# TalkingClock.net
KiCad netlist of a schematic drawn in EAGLE
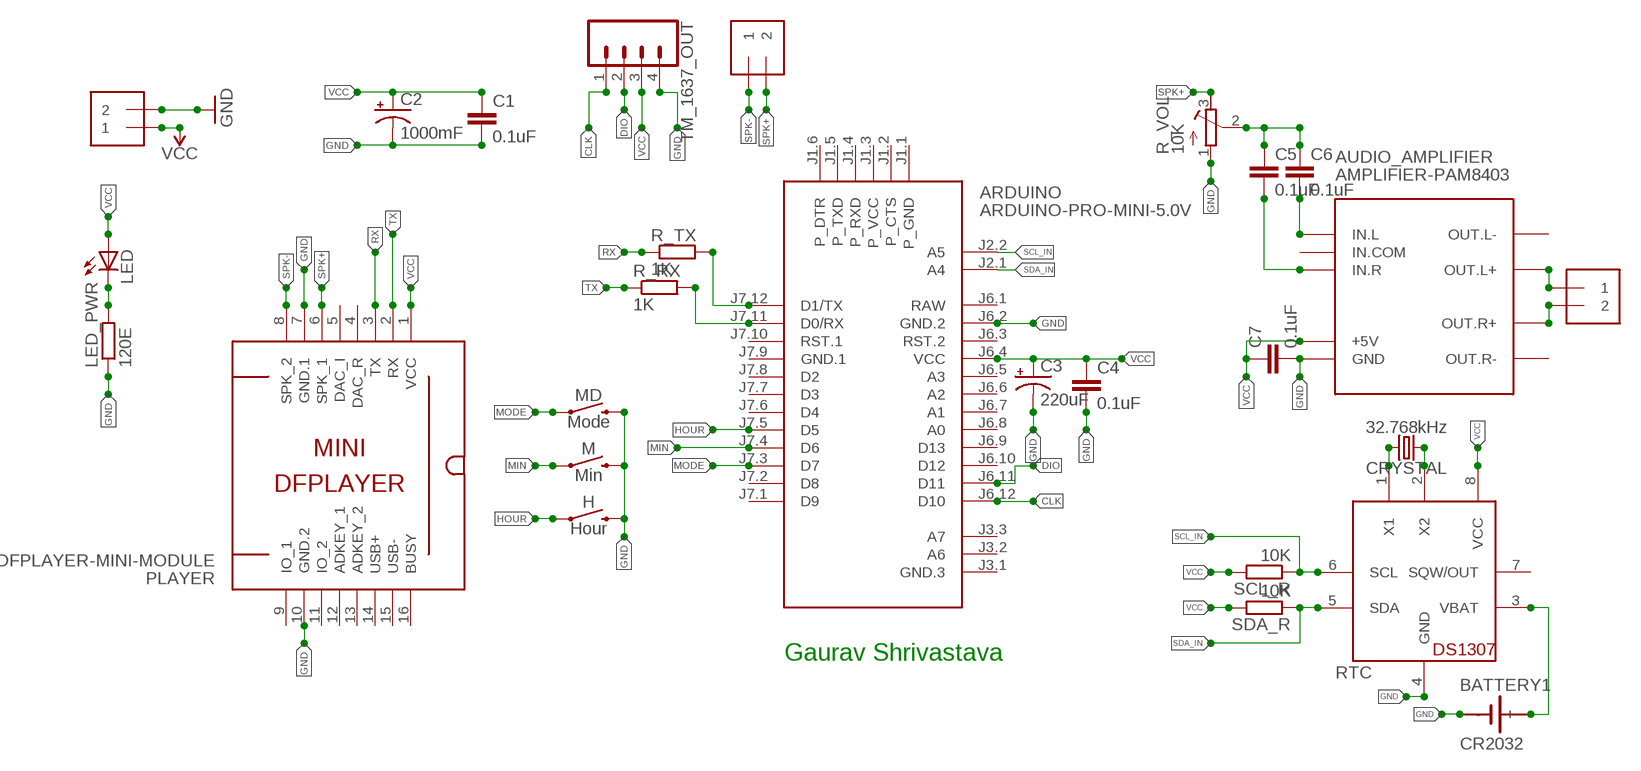
[diagram p0: schematic, sheet 1]

(export (version "E")
  (design (tool "Eeschema 10.0.6"))
  (components
    (comp (ref "ARDUINO")
      (value "ARDUINO-PRO-MINI-5.0V")
      (footprint "eagle-import:ARDUINO-PRO-MINI")
      (libsource (lib "eagle-import") (part "ARDUINO-PRO-MINI-5.0V"))
    )
    (comp (ref "AUDIO_AMPLIFIER")
      (value "AMPLIFIER-PAM8403")
      (footprint "eagle-import:AMPLIFIER-PAM8403")
      (libsource (lib "eagle-import") (part "AMPLIFIER-PAM8403"))
    )
    (comp (ref "BATTERY1")
      (value "CR2032")
      (footprint "eagle-import:SN2032")
      (libsource (lib "eagle-import") (part "SN2032"))
    )
    (comp (ref "C1")
      (value "0.1uF")
      (footprint "eagle-import:CAP-PTH-SMALL-KIT")
      (libsource (lib "eagle-import") (part "0.1UF-KIT-EZ-50V-20%"))
    )
    (comp (ref "C2")
      (value "1000mF")
      (footprint "eagle-import:CPOL-RADIAL-5MM-10MM")
      (libsource (lib "eagle-import") (part "1000UF-RADIAL-5MM-25V-20%"))
    )
    (comp (ref "C3")
      (value "220uF")
      (footprint "eagle-import:CPOL-RADIAL-2.5MM-6.5MM")
      (libsource (lib "eagle-import") (part "100UF-POLAR-RADIAL-2.5MM-25V-20%"))
    )
    (comp (ref "C4")
      (value "0.1uF")
      (footprint "eagle-import:CAP-PTH-SMALL-KIT")
      (libsource (lib "eagle-import") (part "0.1UF-KIT-EZ-50V-20%"))
    )
    (comp (ref "C5")
      (value "0.1uF")
      (footprint "eagle-import:CAP-PTH-SMALL-KIT")
      (libsource (lib "eagle-import") (part "0.1UF-KIT-EZ-50V-20%"))
    )
    (comp (ref "C6")
      (value "0.1uF")
      (footprint "eagle-import:CAP-PTH-SMALL-KIT")
      (libsource (lib "eagle-import") (part "0.1UF-KIT-EZ-50V-20%"))
    )
    (comp (ref "C7")
      (value "0.1uF")
      (footprint "eagle-import:CAP-PTH-SMALL-KIT")
      (libsource (lib "eagle-import") (part "0.1UF-KIT-EZ-50V-20%"))
    )
    (comp (ref "CRYSTAL")
      (value "32.768kHz")
      (footprint "eagle-import:CRYSTAL-PTH-2X6-CYL")
      (libsource (lib "eagle-import") (part "CRYSTAL-32.768KHZPTH-2X6"))
    )
    (comp (ref "H")
      (value "Hour")
      (footprint "eagle-import:TACTILE_SWITCH_PTH_6.0MM")
      (libsource (lib "eagle-import") (part "MOMENTARY-SWITCH-SPST-PTH-6.0MM"))
    )
    (comp (ref "LED")
      (value "LED5MM")
      (footprint "eagle-import:LED5MM")
      (libsource (lib "eagle-import") (part "LED5MM"))
    )
    (comp (ref "LED_PWR")
      (value "120E")
      (footprint "eagle-import:0204_7")
      (libsource (lib "eagle-import") (part "R-EU_0204/7"))
    )
    (comp (ref "M")
      (value "Min")
      (footprint "eagle-import:TACTILE_SWITCH_PTH_6.0MM")
      (libsource (lib "eagle-import") (part "MOMENTARY-SWITCH-SPST-PTH-6.0MM"))
    )
    (comp (ref "MD")
      (value "Mode")
      (footprint "eagle-import:TACTILE_SWITCH_PTH_6.0MM")
      (libsource (lib "eagle-import") (part "MOMENTARY-SWITCH-SPST-PTH-6.0MM"))
    )
    (comp (ref "PLAYER")
      (value "DFPLAYER-MINI-MODULE")
      (footprint "eagle-import:DFPLAYER-MINI-MODULE")
      (libsource (lib "eagle-import") (part "DFPLAYER-MINI-MODULE"))
    )
    (comp (ref "POWER-5-V")
      (value "SPEAKER")
      (footprint "eagle-import:1X2-3.5MM")
      (libsource (lib "eagle-import") (part "1X2-3.5MM"))
    )
    (comp (ref "PRE_SPK_OUT")
      (value "SPEAKER")
      (footprint "eagle-import:1X2-3.5MM")
      (libsource (lib "eagle-import") (part "1X2-3.5MM"))
    )
    (comp (ref "RTC")
      (value "DS1307")
      (footprint "eagle-import:DIL08")
      (libsource (lib "eagle-import") (part "DS1307"))
    )
    (comp (ref "R_RX")
      (value "1K")
      (footprint "eagle-import:0204_7")
      (libsource (lib "eagle-import") (part "R-EU_0204/7"))
    )
    (comp (ref "R_TX")
      (value "1K")
      (footprint "eagle-import:0204_7")
      (libsource (lib "eagle-import") (part "R-EU_0204/7"))
    )
    (comp (ref "R_VOL")
      (value "10K")
      (footprint "eagle-import:RTRIM4G_J")
      (libsource (lib "eagle-import") (part "R-TRIMM4G/J"))
    )
    (comp (ref "SCL_R")
      (value "10K")
      (footprint "eagle-import:0204_7")
      (libsource (lib "eagle-import") (part "R-EU_0204/7"))
    )
    (comp (ref "SDA_R")
      (value "10K")
      (footprint "eagle-import:0204_7")
      (libsource (lib "eagle-import") (part "R-EU_0204/7"))
    )
    (comp (ref "SPEAKER")
      (value "SPEAKER")
      (footprint "eagle-import:1X2-3.5MM")
      (libsource (lib "eagle-import") (part "1X2-3.5MM"))
    )
    (comp (ref "TM_1637_OUT")
      (value "CONN_04")
      (footprint "eagle-import:1X04")
      (libsource (lib "eagle-import") (part "CONN_04"))
    )
  )
  (nets
    (net (code "1") (name "/GND.1") (class "Default")
      (node (ref "ARDUINO") (pin "J7.9") (pinfunction "GND.1_J7.9") (pintype "power_in"))
    )
    (net (code "2") (name "/RAW") (class "Default")
      (node (ref "ARDUINO") (pin "J6.1") (pinfunction "RAW_J6.1") (pintype "power_in"))
    )
    (net (code "3") (name "CLK") (class "Default")
      (node (ref "ARDUINO") (pin "J6.12") (pinfunction "D10_J6.12") (pintype "bidirectional"))
      (node (ref "TM_1637_OUT") (pin "1") (pinfunction "1_1") (pintype "passive"))
    )
    (net (code "4") (name "DIO") (class "Default")
      (node (ref "ARDUINO") (pin "J6.11") (pinfunction "D11_J6.11") (pintype "bidirectional"))
      (node (ref "TM_1637_OUT") (pin "2") (pinfunction "2_2") (pintype "passive"))
    )
    (net (code "5") (name "GND") (class "Default")
      (node (ref "ARDUINO") (pin "J6.2") (pinfunction "GND.2_J6.2") (pintype "power_in"))
      (node (ref "AUDIO_AMPLIFIER") (pin "GND") (pinfunction "GND_GND") (pintype "power_in"))
      (node (ref "BATTERY1") (pin "-") (pinfunction "-_-") (pintype "passive"))
      (node (ref "C1") (pin "2") (pinfunction "2_2") (pintype "passive"))
      (node (ref "C2") (pin "-") (pinfunction "-_-") (pintype "passive"))
      (node (ref "C3") (pin "2") (pinfunction "-_2") (pintype "passive"))
      (node (ref "C4") (pin "2") (pinfunction "2_2") (pintype "passive"))
      (node (ref "C7") (pin "2") (pinfunction "2_2") (pintype "passive"))
      (node (ref "H") (pin "3") (pinfunction "2_3") (pintype "passive"))
      (node (ref "LED_PWR") (pin "1") (pinfunction "1_1") (pintype "passive"))
      (node (ref "M") (pin "3") (pinfunction "2_3") (pintype "passive"))
      (node (ref "MD") (pin "3") (pinfunction "2_3") (pintype "passive"))
      (node (ref "PLAYER") (pin "10") (pinfunction "GND.2_10") (pintype "power_in"))
      (node (ref "PLAYER") (pin "7") (pinfunction "GND.1_7") (pintype "power_in"))
      (node (ref "POWER-5-V") (pin "2") (pinfunction "2_2") (pintype "passive"))
      (node (ref "RTC") (pin "4") (pinfunction "GND_4") (pintype "power_in"))
      (node (ref "R_VOL") (pin "1") (pinfunction "A_1") (pintype "passive"))
      (node (ref "TM_1637_OUT") (pin "4") (pinfunction "4_4") (pintype "passive"))
    )
    (net (code "6") (name "HOUR") (class "Default")
      (node (ref "ARDUINO") (pin "J7.5") (pinfunction "D5_J7.5") (pintype "bidirectional"))
      (node (ref "H") (pin "1") (pinfunction "1_1") (pintype "passive"))
    )
    (net (code "7") (name "MIN") (class "Default")
      (node (ref "ARDUINO") (pin "J7.4") (pinfunction "D6_J7.4") (pintype "bidirectional"))
      (node (ref "M") (pin "1") (pinfunction "1_1") (pintype "passive"))
    )
    (net (code "8") (name "MODE") (class "Default")
      (node (ref "ARDUINO") (pin "J7.3") (pinfunction "D7_J7.3") (pintype "bidirectional"))
      (node (ref "MD") (pin "1") (pinfunction "1_1") (pintype "passive"))
    )
    (net (code "9") (name "Net-(ARDUINO-D0{slash}RX)") (class "Default")
      (node (ref "ARDUINO") (pin "J7.11") (pinfunction "D0/RX_J7.11") (pintype "bidirectional"))
      (node (ref "R_RX") (pin "2") (pinfunction "2_2") (pintype "passive"))
    )
    (net (code "10") (name "Net-(ARDUINO-D1{slash}TX)") (class "Default")
      (node (ref "ARDUINO") (pin "J7.12") (pinfunction "D1/TX_J7.12") (pintype "bidirectional"))
      (node (ref "R_TX") (pin "2") (pinfunction "2_2") (pintype "passive"))
    )
    (net (code "11") (name "Net-(AUDIO_AMPLIFIER-PadIN.L)") (class "Default")
      (node (ref "AUDIO_AMPLIFIER") (pin "IN.L") (pinfunction "IN.L_IN.L") (pintype "input"))
      (node (ref "C6") (pin "2") (pinfunction "2_2") (pintype "passive"))
    )
    (net (code "12") (name "Net-(AUDIO_AMPLIFIER-PadIN.R)") (class "Default")
      (node (ref "AUDIO_AMPLIFIER") (pin "IN.R") (pinfunction "IN.R_IN.R") (pintype "bidirectional"))
      (node (ref "C5") (pin "2") (pinfunction "2_2") (pintype "passive"))
    )
    (net (code "13") (name "Net-(AUDIO_AMPLIFIER-PadOUT.L+)") (class "Default")
      (node (ref "AUDIO_AMPLIFIER") (pin "OUT.L+") (pinfunction "OUT.L+_OUT.L+") (pintype "output"))
      (node (ref "SPEAKER") (pin "1") (pinfunction "1_1") (pintype "passive"))
    )
    (net (code "14") (name "Net-(AUDIO_AMPLIFIER-PadOUT.R+)") (class "Default")
      (node (ref "AUDIO_AMPLIFIER") (pin "OUT.R+") (pinfunction "OUT.R+_OUT.R+") (pintype "output"))
      (node (ref "SPEAKER") (pin "2") (pinfunction "2_2") (pintype "passive"))
    )
    (net (code "15") (name "Net-(LED-C)") (class "Default")
      (node (ref "LED") (pin "K") (pinfunction "C_K") (pintype "passive"))
      (node (ref "LED_PWR") (pin "2") (pinfunction "2_2") (pintype "passive"))
    )
    (net (code "16") (name "Net-(RTC-VBAT)") (class "Default")
      (node (ref "BATTERY1") (pin "+") (pinfunction "+_+") (pintype "passive"))
      (node (ref "RTC") (pin "3") (pinfunction "VBAT_3") (pintype "power_in"))
    )
    (net (code "17") (name "Net-(RTC-X1)") (class "Default")
      (node (ref "CRYSTAL") (pin "2") (pinfunction "2_2") (pintype "passive"))
      (node (ref "RTC") (pin "1") (pinfunction "X1_1") (pintype "passive"))
    )
    (net (code "18") (name "Net-(RTC-X2)") (class "Default")
      (node (ref "CRYSTAL") (pin "1") (pinfunction "1_1") (pintype "passive"))
      (node (ref "RTC") (pin "2") (pinfunction "X2_2") (pintype "passive"))
    )
    (net (code "19") (name "RX") (class "Default")
      (node (ref "PLAYER") (pin "3") (pinfunction "TX_3") (pintype "bidirectional"))
      (node (ref "R_TX") (pin "1") (pinfunction "1_1") (pintype "passive"))
    )
    (net (code "20") (name "SCL_IN") (class "Default")
      (node (ref "ARDUINO") (pin "J2.2") (pinfunction "A5_J2.2") (pintype "bidirectional"))
      (node (ref "RTC") (pin "6") (pinfunction "SCL_6") (pintype "bidirectional"))
      (node (ref "SCL_R") (pin "1") (pinfunction "1_1") (pintype "passive"))
    )
    (net (code "21") (name "SDA_IN") (class "Default")
      (node (ref "ARDUINO") (pin "J2.1") (pinfunction "A4_J2.1") (pintype "bidirectional"))
      (node (ref "RTC") (pin "5") (pinfunction "SDA_5") (pintype "bidirectional"))
      (node (ref "SDA_R") (pin "1") (pinfunction "1_1") (pintype "passive"))
    )
    (net (code "22") (name "SPK+") (class "Default")
      (node (ref "C5") (pin "1") (pinfunction "1_1") (pintype "passive"))
      (node (ref "C6") (pin "1") (pinfunction "1_1") (pintype "passive"))
      (node (ref "PLAYER") (pin "6") (pinfunction "SPK_1_6") (pintype "bidirectional"))
      (node (ref "PRE_SPK_OUT") (pin "2") (pinfunction "2_2") (pintype "passive"))
      (node (ref "R_VOL") (pin "2") (pinfunction "S_2") (pintype "passive"))
      (node (ref "R_VOL") (pin "3") (pinfunction "E_3") (pintype "passive"))
    )
    (net (code "23") (name "SPK-") (class "Default")
      (node (ref "PLAYER") (pin "8") (pinfunction "SPK_2_8") (pintype "bidirectional"))
      (node (ref "PRE_SPK_OUT") (pin "1") (pinfunction "1_1") (pintype "passive"))
    )
    (net (code "24") (name "TX") (class "Default")
      (node (ref "PLAYER") (pin "2") (pinfunction "RX_2") (pintype "bidirectional"))
      (node (ref "R_RX") (pin "1") (pinfunction "1_1") (pintype "passive"))
    )
    (net (code "25") (name "VCC") (class "Default")
      (node (ref "ARDUINO") (pin "J6.4") (pinfunction "VCC_J6.4") (pintype "power_in"))
      (node (ref "AUDIO_AMPLIFIER") (pin "+5V") (pinfunction "+5V_+5V") (pintype "power_in"))
      (node (ref "C1") (pin "1") (pinfunction "1_1") (pintype "passive"))
      (node (ref "C2") (pin "+") (pinfunction "+_+") (pintype "passive"))
      (node (ref "C3") (pin "1") (pinfunction "+_1") (pintype "passive"))
      (node (ref "C4") (pin "1") (pinfunction "1_1") (pintype "passive"))
      (node (ref "C7") (pin "1") (pinfunction "1_1") (pintype "passive"))
      (node (ref "LED") (pin "A") (pinfunction "A_A") (pintype "passive"))
      (node (ref "PLAYER") (pin "1") (pinfunction "VCC_1") (pintype "power_in"))
      (node (ref "POWER-5-V") (pin "1") (pinfunction "1_1") (pintype "passive"))
      (node (ref "RTC") (pin "8") (pinfunction "VCC_8") (pintype "power_in"))
      (node (ref "SCL_R") (pin "2") (pinfunction "2_2") (pintype "passive"))
      (node (ref "SDA_R") (pin "2") (pinfunction "2_2") (pintype "passive"))
      (node (ref "TM_1637_OUT") (pin "3") (pinfunction "3_3") (pintype "passive"))
    )
    (net (code "26") (name "unconnected-(ARDUINO-A0-PadJ6.8)") (class "Default")
      (node (ref "ARDUINO") (pin "J6.8") (pinfunction "A0_J6.8") (pintype "bidirectional"))
    )
    (net (code "27") (name "unconnected-(ARDUINO-A1-PadJ6.7)") (class "Default")
      (node (ref "ARDUINO") (pin "J6.7") (pinfunction "A1_J6.7") (pintype "bidirectional"))
    )
    (net (code "28") (name "unconnected-(ARDUINO-A2-PadJ6.6)") (class "Default")
      (node (ref "ARDUINO") (pin "J6.6") (pinfunction "A2_J6.6") (pintype "bidirectional"))
    )
    (net (code "29") (name "unconnected-(ARDUINO-A3-PadJ6.5)") (class "Default")
      (node (ref "ARDUINO") (pin "J6.5") (pinfunction "A3_J6.5") (pintype "bidirectional"))
    )
    (net (code "30") (name "unconnected-(ARDUINO-A6-PadJ3.2)") (class "Default")
      (node (ref "ARDUINO") (pin "J3.2") (pinfunction "A6_J3.2") (pintype "bidirectional"))
    )
    (net (code "31") (name "unconnected-(ARDUINO-A7-PadJ3.3)") (class "Default")
      (node (ref "ARDUINO") (pin "J3.3") (pinfunction "A7_J3.3") (pintype "bidirectional"))
    )
    (net (code "32") (name "unconnected-(ARDUINO-D2-PadJ7.8)") (class "Default")
      (node (ref "ARDUINO") (pin "J7.8") (pinfunction "D2_J7.8") (pintype "bidirectional"))
    )
    (net (code "33") (name "unconnected-(ARDUINO-D3-PadJ7.7)") (class "Default")
      (node (ref "ARDUINO") (pin "J7.7") (pinfunction "D3_J7.7") (pintype "bidirectional"))
    )
    (net (code "34") (name "unconnected-(ARDUINO-D4-PadJ7.6)") (class "Default")
      (node (ref "ARDUINO") (pin "J7.6") (pinfunction "D4_J7.6") (pintype "bidirectional"))
    )
    (net (code "35") (name "unconnected-(ARDUINO-D8-PadJ7.2)") (class "Default")
      (node (ref "ARDUINO") (pin "J7.2") (pinfunction "D8_J7.2") (pintype "bidirectional"))
    )
    (net (code "36") (name "unconnected-(ARDUINO-D9-PadJ7.1)") (class "Default")
      (node (ref "ARDUINO") (pin "J7.1") (pinfunction "D9_J7.1") (pintype "bidirectional"))
    )
    (net (code "37") (name "unconnected-(ARDUINO-D12-PadJ6.10)") (class "Default")
      (node (ref "ARDUINO") (pin "J6.10") (pinfunction "D12_J6.10") (pintype "bidirectional"))
    )
    (net (code "38") (name "unconnected-(ARDUINO-D13-PadJ6.9)") (class "Default")
      (node (ref "ARDUINO") (pin "J6.9") (pinfunction "D13_J6.9") (pintype "bidirectional"))
    )
    (net (code "39") (name "unconnected-(ARDUINO-GND.3-PadJ3.1)") (class "Default")
      (node (ref "ARDUINO") (pin "J3.1") (pinfunction "GND.3_J3.1") (pintype "bidirectional"))
    )
    (net (code "40") (name "unconnected-(ARDUINO-P_CTS-PadJ1.2)") (class "Default")
      (node (ref "ARDUINO") (pin "J1.2") (pinfunction "P_CTS_J1.2") (pintype "bidirectional"))
    )
    (net (code "41") (name "unconnected-(ARDUINO-P_DTR-PadJ1.6)") (class "Default")
      (node (ref "ARDUINO") (pin "J1.6") (pinfunction "P_DTR_J1.6") (pintype "bidirectional"))
    )
    (net (code "42") (name "unconnected-(ARDUINO-P_GND-PadJ1.1)") (class "Default")
      (node (ref "ARDUINO") (pin "J1.1") (pinfunction "P_GND_J1.1") (pintype "bidirectional"))
    )
    (net (code "43") (name "unconnected-(ARDUINO-P_RXD-PadJ1.4)") (class "Default")
      (node (ref "ARDUINO") (pin "J1.4") (pinfunction "P_RXD_J1.4") (pintype "bidirectional"))
    )
    (net (code "44") (name "unconnected-(ARDUINO-P_TXD-PadJ1.5)") (class "Default")
      (node (ref "ARDUINO") (pin "J1.5") (pinfunction "P_TXD_J1.5") (pintype "bidirectional"))
    )
    (net (code "45") (name "unconnected-(ARDUINO-P_VCC-PadJ1.3)") (class "Default")
      (node (ref "ARDUINO") (pin "J1.3") (pinfunction "P_VCC_J1.3") (pintype "bidirectional"))
    )
    (net (code "46") (name "unconnected-(ARDUINO-RST.1-PadJ7.10)") (class "Default")
      (node (ref "ARDUINO") (pin "J7.10") (pinfunction "RST.1_J7.10") (pintype "bidirectional"))
    )
    (net (code "47") (name "unconnected-(ARDUINO-RST.2-PadJ6.3)") (class "Default")
      (node (ref "ARDUINO") (pin "J6.3") (pinfunction "RST.2_J6.3") (pintype "bidirectional"))
    )
    (net (code "48") (name "unconnected-(AUDIO_AMPLIFIER-PadIN.COM)") (class "Default")
      (node (ref "AUDIO_AMPLIFIER") (pin "IN.COM") (pinfunction "IN.COM_IN.COM") (pintype "input"))
    )
    (net (code "49") (name "unconnected-(AUDIO_AMPLIFIER-PadOUT.L-)") (class "Default")
      (node (ref "AUDIO_AMPLIFIER") (pin "OUT.L-") (pinfunction "OUT.L-_OUT.L-") (pintype "output"))
    )
    (net (code "50") (name "unconnected-(AUDIO_AMPLIFIER-PadOUT.R-)") (class "Default")
      (node (ref "AUDIO_AMPLIFIER") (pin "OUT.R-") (pinfunction "OUT.R-_OUT.R-") (pintype "output"))
    )
    (net (code "51") (name "unconnected-(PLAYER-ADKEY_1-Pad12)") (class "Default")
      (node (ref "PLAYER") (pin "12") (pinfunction "ADKEY_1_12") (pintype "bidirectional"))
    )
    (net (code "52") (name "unconnected-(PLAYER-ADKEY_2-Pad13)") (class "Default")
      (node (ref "PLAYER") (pin "13") (pinfunction "ADKEY_2_13") (pintype "bidirectional"))
    )
    (net (code "53") (name "unconnected-(PLAYER-BUSY-Pad16)") (class "Default")
      (node (ref "PLAYER") (pin "16") (pinfunction "BUSY_16") (pintype "bidirectional"))
    )
    (net (code "54") (name "unconnected-(PLAYER-DAC_I-Pad5)") (class "Default")
      (node (ref "PLAYER") (pin "5") (pinfunction "DAC_I_5") (pintype "bidirectional"))
    )
    (net (code "55") (name "unconnected-(PLAYER-DAC_R-Pad4)") (class "Default")
      (node (ref "PLAYER") (pin "4") (pinfunction "DAC_R_4") (pintype "bidirectional"))
    )
    (net (code "56") (name "unconnected-(PLAYER-IO_1-Pad9)") (class "Default")
      (node (ref "PLAYER") (pin "9") (pinfunction "IO_1_9") (pintype "bidirectional"))
    )
    (net (code "57") (name "unconnected-(PLAYER-IO_2-Pad11)") (class "Default")
      (node (ref "PLAYER") (pin "11") (pinfunction "IO_2_11") (pintype "bidirectional"))
    )
    (net (code "58") (name "unconnected-(PLAYER-USB+-Pad14)") (class "Default")
      (node (ref "PLAYER") (pin "14") (pinfunction "USB+_14") (pintype "bidirectional"))
    )
    (net (code "59") (name "unconnected-(PLAYER-USB--Pad15)") (class "Default")
      (node (ref "PLAYER") (pin "15") (pinfunction "USB-_15") (pintype "bidirectional"))
    )
    (net (code "60") (name "unconnected-(RTC-SQW{slash}OUT-Pad7)") (class "Default")
      (node (ref "RTC") (pin "7") (pinfunction "SQW/OUT_7") (pintype "bidirectional"))
    )
  )
)
